# rf_tx_pa.net
KiCad netlist of a schematic drawn in Altium Designer
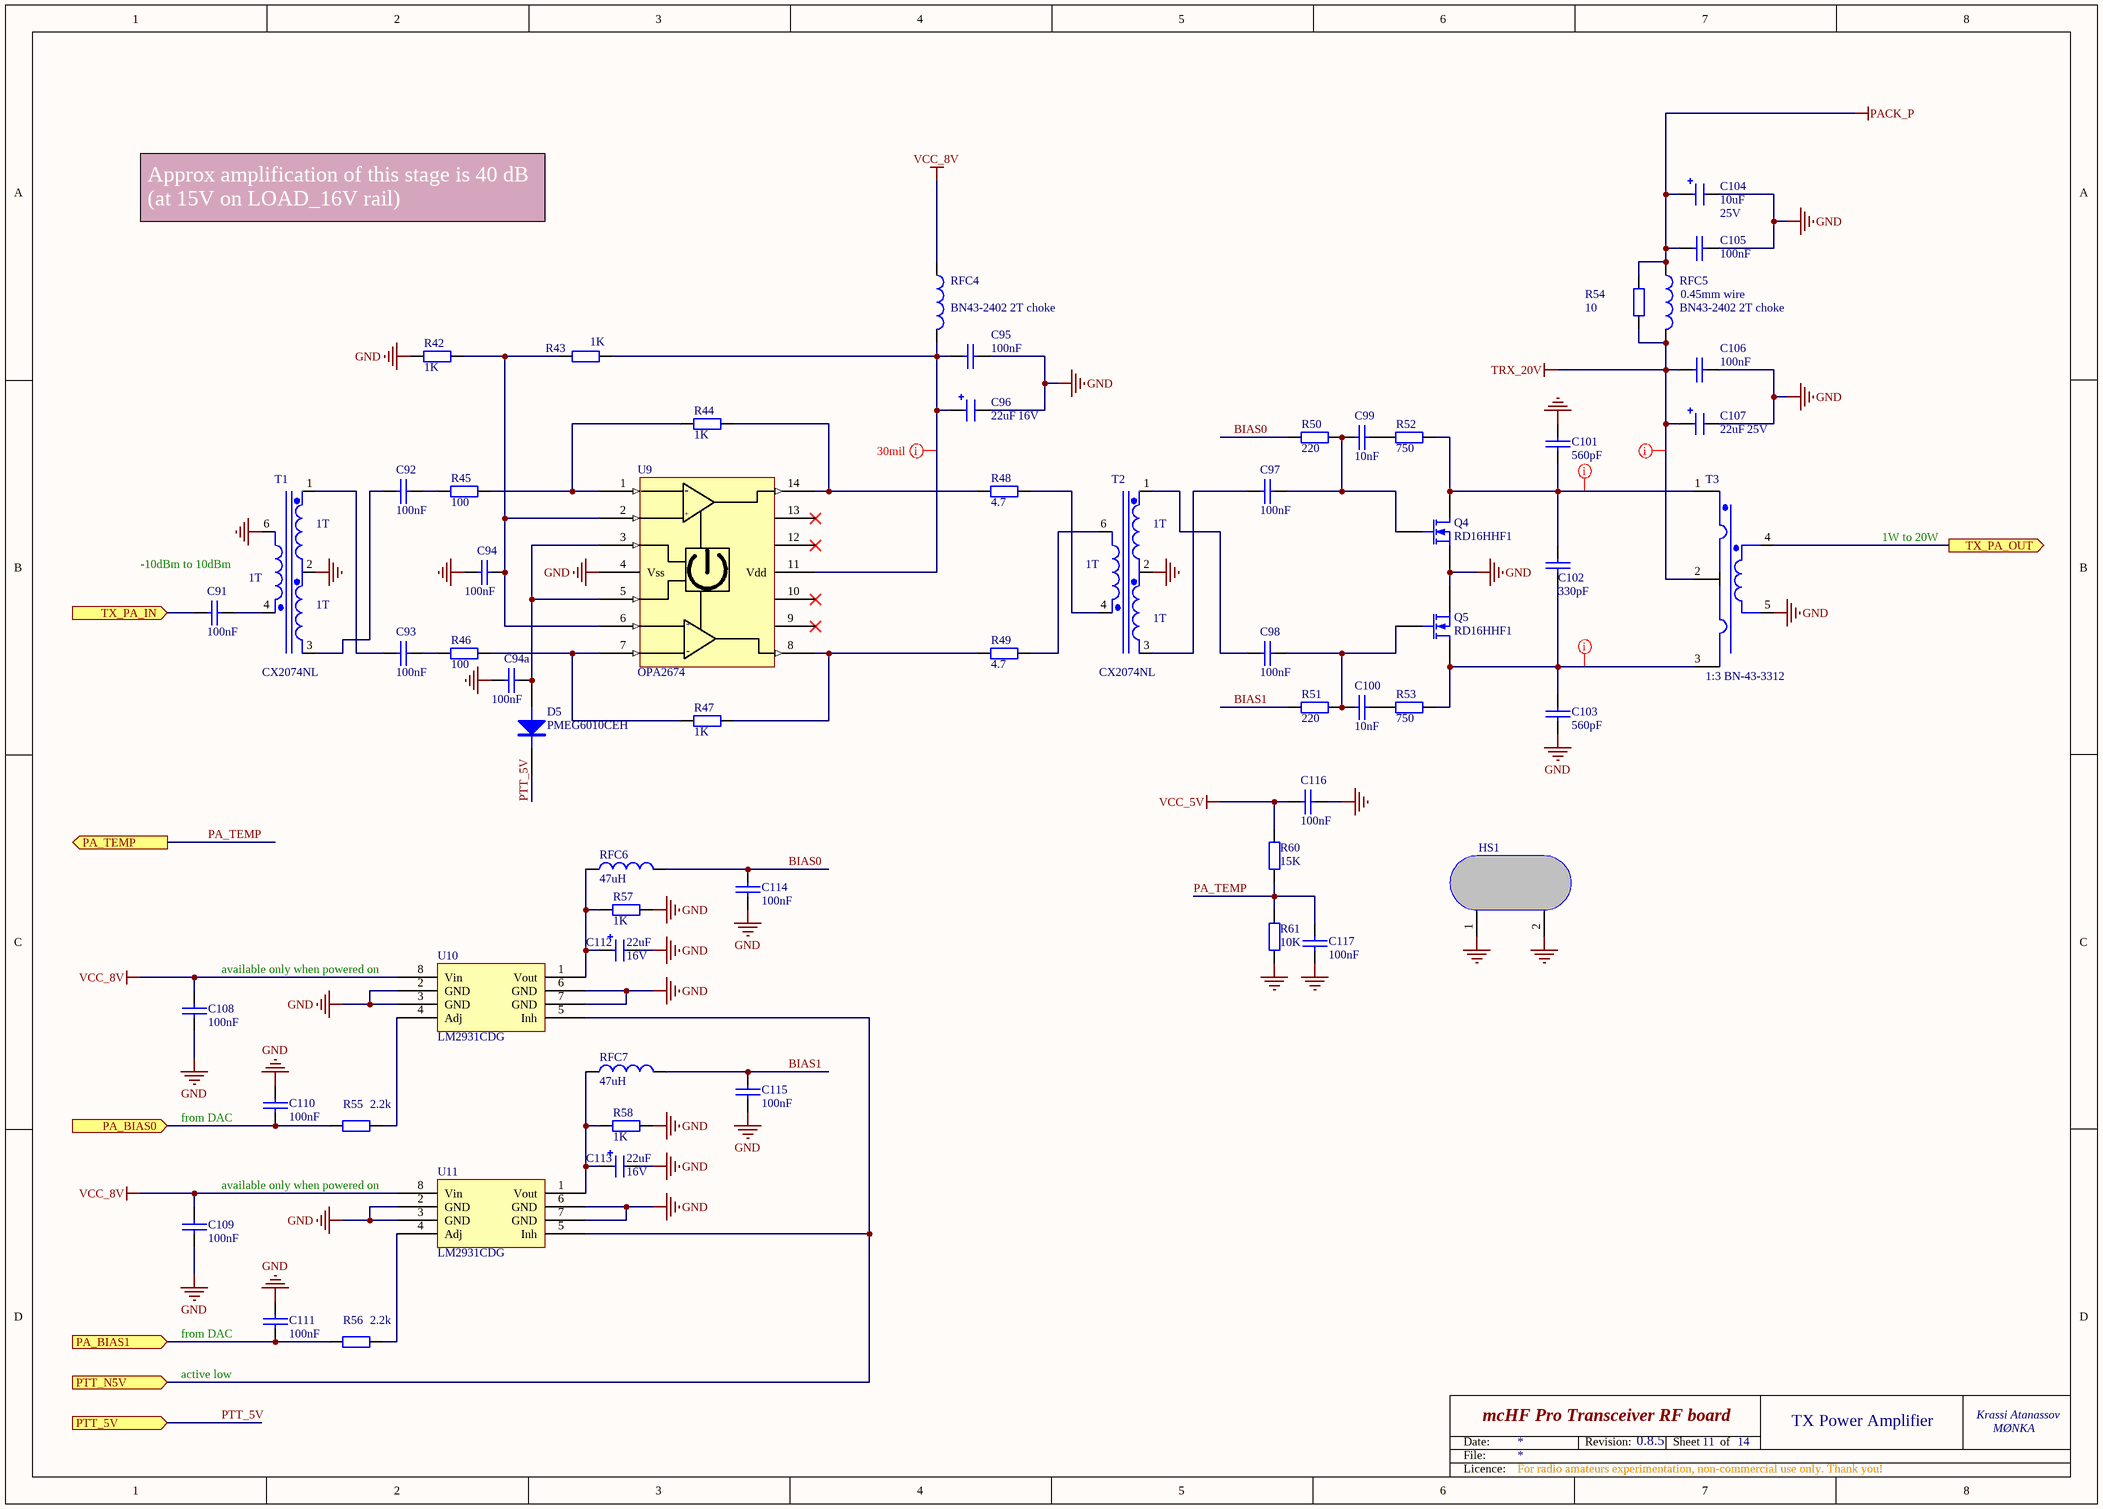
[diagram p0: rf_tx_pa.SchDoc]

(export (version "E")
  (design (tool "Eeschema 10.0.6"))
  (components
    (comp (ref "C91")
      (value "100nF")
      (footprint "0805")
      (description "Capacitor")
      (libsource (lib "mcHF_rf") (part "CAP"))
    )
    (comp (ref "C92")
      (value "100nF")
      (footprint "0805")
      (description "Capacitor")
      (fields (field (name "VOLTAGE") "100V"))
      (libsource (lib "mcHF_rf") (part "CAP"))
    )
    (comp (ref "C93")
      (value "100nF")
      (footprint "0805")
      (description "Capacitor")
      (fields (field (name "VOLTAGE") "100V"))
      (libsource (lib "mcHF_rf") (part "CAP"))
    )
    (comp (ref "C94")
      (value "100nF")
      (footprint "0805")
      (description "Capacitor")
      (fields (field (name "VOLTAGE") "100V"))
      (libsource (lib "mcHF_rf") (part "CAP"))
    )
    (comp (ref "C94a")
      (value "100nF")
      (footprint "0805")
      (description "Capacitor")
      (fields (field (name "VOLTAGE") "100V"))
      (libsource (lib "mcHF_rf") (part "CAP"))
    )
    (comp (ref "C95")
      (value "100nF")
      (footprint "0805")
      (description "Capacitor")
      (fields (field (name "VOLTAGE") "100V"))
      (libsource (lib "mcHF_rf") (part "CAP"))
    )
    (comp (ref "C96")
      (value "22uF")
      (footprint "1206_Elec_Cap")
      (description "Electrolitic capacitor")
      (fields (field (name "VOLTAGE") "16V"))
      (libsource (lib "mcHF_rf") (part "CAP-POL"))
    )
    (comp (ref "C97")
      (value "100nF")
      (footprint "0805")
      (description "Capacitor")
      (fields (field (name "VOLTAGE") "100V"))
      (libsource (lib "mcHF_rf") (part "CAP"))
    )
    (comp (ref "C98")
      (value "100nF")
      (footprint "0805")
      (description "Capacitor")
      (fields (field (name "VOLTAGE") "100V"))
      (libsource (lib "mcHF_rf") (part "CAP"))
    )
    (comp (ref "C99")
      (value "10nF")
      (footprint "0805")
      (description "Capacitor")
      (fields (field (name "VOLTAGE") "100V"))
      (libsource (lib "mcHF_rf") (part "CAP"))
    )
    (comp (ref "C100")
      (value "10nF")
      (footprint "0805")
      (description "Capacitor")
      (fields (field (name "VOLTAGE") "100V"))
      (libsource (lib "mcHF_rf") (part "CAP"))
    )
    (comp (ref "C101")
      (value "560pF")
      (footprint "0805")
      (description "Capacitor")
      (fields (field (name "VOLTAGE") "100V"))
      (libsource (lib "mcHF_rf") (part "CAP"))
    )
    (comp (ref "C102")
      (value "330pF")
      (footprint "0805")
      (description "Capacitor")
      (fields (field (name "VOLTAGE") "100V"))
      (libsource (lib "mcHF_rf") (part "CAP"))
    )
    (comp (ref "C103")
      (value "560pF")
      (footprint "0805")
      (description "Capacitor")
      (fields (field (name "VOLTAGE") "100V"))
      (libsource (lib "mcHF_rf") (part "CAP"))
    )
    (comp (ref "C104")
      (value "10uF")
      (footprint "1206_Elec_Cap")
      (description "Electrolitic capacitor")
      (fields (field (name "VOLTAGE") "25V"))
      (libsource (lib "mcHF_rf") (part "CAP-POL"))
    )
    (comp (ref "C105")
      (value "100nF")
      (footprint "0805")
      (description "Capacitor")
      (fields (field (name "VOLTAGE") "100V"))
      (libsource (lib "mcHF_rf") (part "CAP"))
    )
    (comp (ref "C106")
      (value "100nF")
      (footprint "0805")
      (description "Capacitor")
      (fields (field (name "VOLTAGE") "100V"))
      (libsource (lib "mcHF_rf") (part "CAP"))
    )
    (comp (ref "C107")
      (value "22uF")
      (footprint "1206_Elec_Cap")
      (description "Electrolitic capacitor")
      (fields (field (name "VOLTAGE") "25V"))
      (libsource (lib "mcHF_rf") (part "CAP-POL"))
    )
    (comp (ref "C108")
      (value "100nF")
      (footprint "0805")
      (description "Capacitor")
      (fields (field (name "VOLTAGE") "100V"))
      (libsource (lib "mcHF_rf") (part "CAP"))
    )
    (comp (ref "C109")
      (value "100nF")
      (footprint "0805")
      (description "Capacitor")
      (fields (field (name "VOLTAGE") "100V"))
      (libsource (lib "mcHF_rf") (part "CAP"))
    )
    (comp (ref "C110")
      (value "100nF")
      (footprint "0805")
      (description "Capacitor")
      (libsource (lib "mcHF_rf") (part "CAP"))
    )
    (comp (ref "C111")
      (value "100nF")
      (footprint "0805")
      (description "Capacitor")
      (libsource (lib "mcHF_rf") (part "CAP"))
    )
    (comp (ref "C112")
      (value "22uF")
      (footprint "1206_Elec_Cap")
      (description "Electrolitic capacitor")
      (fields (field (name "VOLTAGE") "16V"))
      (libsource (lib "mcHF_rf") (part "CAP-POL"))
    )
    (comp (ref "C113")
      (value "22uF")
      (footprint "1206_Elec_Cap")
      (description "Electrolitic capacitor")
      (fields (field (name "VOLTAGE") "16V"))
      (libsource (lib "mcHF_rf") (part "CAP-POL"))
    )
    (comp (ref "C114")
      (value "100nF")
      (footprint "0805")
      (description "Capacitor")
      (fields (field (name "VOLTAGE") "100V"))
      (libsource (lib "mcHF_rf") (part "CAP"))
    )
    (comp (ref "C115")
      (value "100nF")
      (footprint "0805")
      (description "Capacitor")
      (fields (field (name "VOLTAGE") "100V"))
      (libsource (lib "mcHF_rf") (part "CAP"))
    )
    (comp (ref "C116")
      (value "100nF")
      (footprint "0805")
      (description "Capacitor")
      (fields (field (name "VOLTAGE") "100V"))
      (libsource (lib "mcHF_rf") (part "CAP"))
    )
    (comp (ref "C117")
      (value "100nF")
      (footprint "0805")
      (description "Capacitor")
      (fields (field (name "VOLTAGE") "100V"))
      (libsource (lib "mcHF_rf") (part "CAP"))
    )
    (comp (ref "D5")
      (value "PMEG6010CEH")
      (footprint "SOD87")
      (description "DIODE, SCHOTTKY, 1A, 60V, SOD-123F")
      (libsource (lib "mcHF_rf") (part "PMEG6010CEH"))
    )
    (comp (ref "HS1")
      (value "RD16HHF1x2")
      (footprint "TO-220_5_DUAL_HS")
      (description "RF MOSFET x2 heatsink")
      (libsource (lib "__rf") (part "RD16HHF1_DUAL_HEATSINK"))
    )
    (comp (ref "Q4")
      (value "RD16HHF1")
      (footprint "TO-220c")
      (description "Silicon RF Power MOS FET")
      (libsource (lib "__rf") (part "RD16HHF1"))
    )
    (comp (ref "Q5")
      (value "RD16HHF1")
      (footprint "TO-220c")
      (description "Silicon RF Power MOS FET")
      (libsource (lib "__rf") (part "RD16HHF1"))
    )
    (comp (ref "R42")
      (value "1K")
      (footprint "0805")
      (description "Resistor")
      (libsource (lib "") (part "RES_2"))
    )
    (comp (ref "R43")
      (value "1K")
      (footprint "0805")
      (description "Resistor")
      (libsource (lib "mcHF_rf") (part "RES"))
    )
    (comp (ref "R44")
      (value "1K")
      (footprint "0805")
      (description "Resistor")
      (libsource (lib "mcHF_rf") (part "RES"))
    )
    (comp (ref "R45")
      (value "100")
      (footprint "0805")
      (description "Resistor")
      (libsource (lib "mcHF_rf") (part "RES"))
    )
    (comp (ref "R46")
      (value "100")
      (footprint "0805")
      (description "Resistor")
      (libsource (lib "mcHF_rf") (part "RES"))
    )
    (comp (ref "R47")
      (value "1K")
      (footprint "0805")
      (description "Resistor")
      (libsource (lib "mcHF_rf") (part "RES"))
    )
    (comp (ref "R48")
      (value "4.7")
      (footprint "0805")
      (description "Resistor")
      (libsource (lib "mcHF_rf") (part "RES"))
    )
    (comp (ref "R49")
      (value "4.7")
      (footprint "0805")
      (description "Resistor")
      (libsource (lib "mcHF_rf") (part "RES"))
    )
    (comp (ref "R50")
      (value "220")
      (footprint "0805")
      (description "Resistor")
      (libsource (lib "mcHF_rf") (part "RES"))
    )
    (comp (ref "R51")
      (value "220")
      (footprint "0805")
      (description "Resistor")
      (libsource (lib "mcHF_rf") (part "RES"))
    )
    (comp (ref "R52")
      (value "750")
      (footprint "0805")
      (description "Resistor")
      (libsource (lib "mcHF_rf") (part "RES"))
    )
    (comp (ref "R53")
      (value "750")
      (footprint "0805")
      (description "Resistor")
      (libsource (lib "mcHF_rf") (part "RES"))
    )
    (comp (ref "R54")
      (value "10")
      (footprint "0805")
      (description "Resistor")
      (libsource (lib "") (part "RES_3"))
    )
    (comp (ref "R55")
      (value "2.2k")
      (footprint "0805")
      (description "Resistor")
      (libsource (lib "") (part "RES_2"))
    )
    (comp (ref "R56")
      (value "2.2k")
      (footprint "0805")
      (description "Resistor")
      (libsource (lib "") (part "RES_2"))
    )
    (comp (ref "R57")
      (value "1K")
      (footprint "0805")
      (description "Resistor")
      (libsource (lib "mcHF_rf") (part "RES"))
    )
    (comp (ref "R58")
      (value "1K")
      (footprint "0805")
      (description "Resistor")
      (libsource (lib "mcHF_rf") (part "RES"))
    )
    (comp (ref "R60")
      (value "15K")
      (footprint "0805")
      (description "Resistor")
      (libsource (lib "") (part "RES_1"))
    )
    (comp (ref "R61")
      (value "10K")
      (footprint "0805")
      (description "Resistor")
      (libsource (lib "") (part "RES_1"))
    )
    (comp (ref "RFC4")
      (value "BN43-2402 2T choke")
      (footprint "F_Bead_Flat")
      (description "BN43-2402 1t choke")
      (libsource (lib "mcHF_rf") (part "FER_BEAD"))
    )
    (comp (ref "RFC5")
      (value "BN43-2402 2T choke")
      (footprint "F_Bead")
      (description "BN43-2402 1t choke")
      (libsource (lib "mcHF_rf") (part "FER_BEAD"))
    )
    (comp (ref "RFC6")
      (value "47uH")
      (footprint "0805")
      (description "INDUCTOR, SIGNAL LINE, 4.7UH, 1005")
      (libsource (lib "mcHF_rf") (part "TDK-NLV25T"))
    )
    (comp (ref "RFC7")
      (value "47uH")
      (footprint "0805")
      (description "INDUCTOR, SIGNAL LINE, 4.7UH, 1005")
      (libsource (lib "mcHF_rf") (part "TDK-NLV25T"))
    )
    (comp (ref "T1")
      (value "CX2074NL")
      (footprint "SOP5_NEW1")
      (description "Transformer 4:1")
      (libsource (lib "mcHF_rf") (part "CX2074NL"))
    )
    (comp (ref "T2")
      (value "CX2074NL")
      (footprint "SOP5_NEW1")
      (description "Transformer 4:1")
      (libsource (lib "mcHF_rf") (part "CX2074NL"))
    )
    (comp (ref "T3")
      (value "1:3 BN-43-3312")
      (footprint "PA_OUT_TRM")
      (description "1:3 BN-43-3312 transformer")
      (libsource (lib "__rf") (part "PA_OUT_TR"))
    )
    (comp (ref "U9")
      (value "OPA2674")
      (footprint "SO-14-PRO")
      (description "Dual Wideband, High Output Current\r\nOperational Amplifier with Current Limit")
      (libsource (lib "__rf") (part "OPA2674"))
    )
    (comp (ref "U10")
      (value "LM2931CDG")
      (footprint "SO-8-PRO")
      (description "100 mA, Adjustable Output,  LDO Voltage Regulator with  60 V Load Dump Protection")
      (libsource (lib "mcHF_rf") (part "LM2931CDG"))
    )
    (comp (ref "U11")
      (value "LM2931CDG")
      (footprint "SO-8-PRO")
      (description "100 mA, Adjustable Output,  LDO Voltage Regulator with  60 V Load Dump Protection")
      (libsource (lib "mcHF_rf") (part "LM2931CDG"))
    )
  )
  (nets
    (net (code "1") (name "/BIAS0") (class "Default")
      (node (ref "C114") (pin "2") (pinfunction "2_2") (pintype "passive"))
      (node (ref "R50") (pin "2") (pinfunction "2_2") (pintype "passive"))
      (node (ref "RFC6") (pin "2") (pinfunction "2_2") (pintype "passive"))
    )
    (net (code "2") (name "/BIAS1") (class "Default")
      (node (ref "C115") (pin "2") (pinfunction "2_2") (pintype "passive"))
      (node (ref "R51") (pin "2") (pinfunction "2_2") (pintype "passive"))
      (node (ref "RFC7") (pin "2") (pinfunction "2_2") (pintype "passive"))
    )
    (net (code "3") (name "/PA_BIAS0") (class "Default")
      (node (ref "C110") (pin "1") (pinfunction "1_1") (pintype "passive"))
      (node (ref "R55") (pin "1") (pinfunction "1_1") (pintype "passive"))
    )
    (net (code "4") (name "/PA_BIAS1") (class "Default")
      (node (ref "C111") (pin "2") (pinfunction "2_2") (pintype "passive"))
      (node (ref "R56") (pin "1") (pinfunction "1_1") (pintype "passive"))
    )
    (net (code "5") (name "/PA_TEMP") (class "Default")
      (node (ref "C117") (pin "1") (pinfunction "1_1") (pintype "passive"))
      (node (ref "R60") (pin "2") (pinfunction "2_2") (pintype "passive"))
      (node (ref "R61") (pin "1") (pinfunction "1_1") (pintype "passive"))
    )
    (net (code "6") (name "/PTT_5V") (class "Default")
      (node (ref "D5") (pin "2") (pinfunction "K_2") (pintype "passive"))
    )
    (net (code "7") (name "/PTT_N5V") (class "Default")
      (node (ref "U10") (pin "5") (pinfunction "Inh_5") (pintype "passive"))
      (node (ref "U11") (pin "5") (pinfunction "Inh_5") (pintype "passive"))
    )
    (net (code "8") (name "/TX_PA_IN") (class "Default")
      (node (ref "C91") (pin "2") (pinfunction "2_2") (pintype "passive"))
    )
    (net (code "9") (name "/TX_PA_OUT") (class "Default")
      (node (ref "T3") (pin "4") (pinfunction "Sec+_4") (pintype "passive"))
    )
    (net (code "10") (name "GND") (class "Default")
      (node (ref "C101") (pin "1") (pinfunction "1_1") (pintype "passive"))
      (node (ref "C103") (pin "2") (pinfunction "2_2") (pintype "passive"))
      (node (ref "C104") (pin "2") (pinfunction "2_2") (pintype "passive"))
      (node (ref "C105") (pin "1") (pinfunction "1_1") (pintype "passive"))
      (node (ref "C106") (pin "1") (pinfunction "1_1") (pintype "passive"))
      (node (ref "C107") (pin "2") (pinfunction "2_2") (pintype "passive"))
      (node (ref "C108") (pin "2") (pinfunction "2_2") (pintype "passive"))
      (node (ref "C109") (pin "2") (pinfunction "2_2") (pintype "passive"))
      (node (ref "C110") (pin "2") (pinfunction "2_2") (pintype "passive"))
      (node (ref "C111") (pin "1") (pinfunction "1_1") (pintype "passive"))
      (node (ref "C112") (pin "2") (pinfunction "2_2") (pintype "passive"))
      (node (ref "C113") (pin "2") (pinfunction "2_2") (pintype "passive"))
      (node (ref "C114") (pin "1") (pinfunction "1_1") (pintype "passive"))
      (node (ref "C115") (pin "1") (pinfunction "1_1") (pintype "passive"))
      (node (ref "C116") (pin "1") (pinfunction "1_1") (pintype "passive"))
      (node (ref "C117") (pin "2") (pinfunction "2_2") (pintype "passive"))
      (node (ref "C94") (pin "1") (pinfunction "1_1") (pintype "passive"))
      (node (ref "C94a") (pin "1") (pinfunction "1_1") (pintype "passive"))
      (node (ref "C95") (pin "1") (pinfunction "1_1") (pintype "passive"))
      (node (ref "C96") (pin "2") (pinfunction "2_2") (pintype "passive"))
      (node (ref "HS1") (pin "1") (pinfunction "GND_1") (pintype "passive"))
      (node (ref "HS1") (pin "2") (pinfunction "GND_2") (pintype "passive"))
      (node (ref "Q4") (pin "2") (pinfunction "S_2") (pintype "passive"))
      (node (ref "Q5") (pin "2") (pinfunction "S_2") (pintype "passive"))
      (node (ref "R42") (pin "1") (pinfunction "1_1") (pintype "passive"))
      (node (ref "R57") (pin "1") (pinfunction "1_1") (pintype "passive"))
      (node (ref "R58") (pin "1") (pinfunction "1_1") (pintype "passive"))
      (node (ref "R61") (pin "2") (pinfunction "2_2") (pintype "passive"))
      (node (ref "T1") (pin "2") (pinfunction "SecCmn_2") (pintype "passive"))
      (node (ref "T1") (pin "6") (pinfunction "Pri+_6") (pintype "passive"))
      (node (ref "T2") (pin "2") (pinfunction "SecCmn_2") (pintype "passive"))
      (node (ref "T3") (pin "5") (pinfunction "Sec-_5") (pintype "passive"))
      (node (ref "U10") (pin "2") (pinfunction "GND_2") (pintype "passive"))
      (node (ref "U10") (pin "3") (pinfunction "GND_3") (pintype "passive"))
      (node (ref "U10") (pin "6") (pinfunction "GND_6") (pintype "passive"))
      (node (ref "U10") (pin "7") (pinfunction "GND_7") (pintype "passive"))
      (node (ref "U11") (pin "2") (pinfunction "GND_2") (pintype "passive"))
      (node (ref "U11") (pin "3") (pinfunction "GND_3") (pintype "passive"))
      (node (ref "U11") (pin "6") (pinfunction "GND_6") (pintype "passive"))
      (node (ref "U11") (pin "7") (pinfunction "GND_7") (pintype "passive"))
      (node (ref "U9") (pin "4") (pinfunction "Vss_4") (pintype "power_in"))
    )
    (net (code "11") (name "Net-(C92-Pad2)") (class "Default")
      (node (ref "C92") (pin "2") (pinfunction "2_2") (pintype "passive"))
      (node (ref "R45") (pin "2") (pinfunction "2_2") (pintype "passive"))
    )
    (net (code "12") (name "Net-(C93-Pad2)") (class "Default")
      (node (ref "C93") (pin "2") (pinfunction "2_2") (pintype "passive"))
      (node (ref "R46") (pin "2") (pinfunction "2_2") (pintype "passive"))
    )
    (net (code "13") (name "Net-(C94-Pad2)") (class "Default")
      (node (ref "C94") (pin "2") (pinfunction "2_2") (pintype "passive"))
      (node (ref "R42") (pin "2") (pinfunction "2_2") (pintype "passive"))
      (node (ref "R43") (pin "2") (pinfunction "2_2") (pintype "passive"))
      (node (ref "U9") (pin "2") (pintype "input"))
      (node (ref "U9") (pin "6") (pintype "input"))
    )
    (net (code "14") (name "Net-(C99-Pad2)") (class "Default")
      (node (ref "C99") (pin "2") (pinfunction "2_2") (pintype "passive"))
      (node (ref "R52") (pin "2") (pinfunction "2_2") (pintype "passive"))
    )
    (net (code "15") (name "Net-(C100-Pad2)") (class "Default")
      (node (ref "C100") (pin "2") (pinfunction "2_2") (pintype "passive"))
      (node (ref "R53") (pin "2") (pinfunction "2_2") (pintype "passive"))
    )
    (net (code "16") (name "Net-(D5-A)") (class "Default")
      (node (ref "C94a") (pin "2") (pinfunction "2_2") (pintype "passive"))
      (node (ref "D5") (pin "1") (pinfunction "A_1") (pintype "passive"))
      (node (ref "U9") (pin "3") (pintype "input"))
      (node (ref "U9") (pin "5") (pintype "input"))
    )
    (net (code "17") (name "Net-(Q4-D)") (class "Default")
      (node (ref "C101") (pin "2") (pinfunction "2_2") (pintype "passive"))
      (node (ref "C102") (pin "1") (pinfunction "1_1") (pintype "passive"))
      (node (ref "Q4") (pin "3") (pinfunction "D_3") (pintype "passive"))
      (node (ref "R52") (pin "1") (pinfunction "1_1") (pintype "passive"))
      (node (ref "T3") (pin "1") (pinfunction "Pri_0_deg_1") (pintype "passive"))
    )
    (net (code "18") (name "Net-(Q4-G)") (class "Default")
      (node (ref "C97") (pin "1") (pinfunction "1_1") (pintype "passive"))
      (node (ref "C99") (pin "1") (pinfunction "1_1") (pintype "passive"))
      (node (ref "Q4") (pin "1") (pinfunction "G_1") (pintype "passive"))
      (node (ref "R50") (pin "1") (pinfunction "1_1") (pintype "passive"))
    )
    (net (code "19") (name "Net-(Q5-D)") (class "Default")
      (node (ref "C102") (pin "2") (pinfunction "2_2") (pintype "passive"))
      (node (ref "C103") (pin "1") (pinfunction "1_1") (pintype "passive"))
      (node (ref "Q5") (pin "3") (pinfunction "D_3") (pintype "passive"))
      (node (ref "R53") (pin "1") (pinfunction "1_1") (pintype "passive"))
      (node (ref "T3") (pin "3") (pinfunction "Pri_180_deg_3") (pintype "passive"))
    )
    (net (code "20") (name "Net-(Q5-G)") (class "Default")
      (node (ref "C100") (pin "1") (pinfunction "1_1") (pintype "passive"))
      (node (ref "C98") (pin "1") (pinfunction "1_1") (pintype "passive"))
      (node (ref "Q5") (pin "1") (pinfunction "G_1") (pintype "passive"))
      (node (ref "R51") (pin "1") (pinfunction "1_1") (pintype "passive"))
    )
    (net (code "21") (name "Net-(R44-Pad1)") (class "Default")
      (node (ref "R44") (pin "1") (pinfunction "1_1") (pintype "passive"))
      (node (ref "R48") (pin "2") (pinfunction "2_2") (pintype "passive"))
      (node (ref "U9") (pin "14") (pintype "output"))
    )
    (net (code "22") (name "Net-(R44-Pad2)") (class "Default")
      (node (ref "R44") (pin "2") (pinfunction "2_2") (pintype "passive"))
      (node (ref "R45") (pin "1") (pinfunction "1_1") (pintype "passive"))
      (node (ref "U9") (pin "1") (pintype "input"))
    )
    (net (code "23") (name "Net-(R46-Pad1)") (class "Default")
      (node (ref "R46") (pin "1") (pinfunction "1_1") (pintype "passive"))
      (node (ref "R47") (pin "2") (pinfunction "2_2") (pintype "passive"))
      (node (ref "U9") (pin "7") (pintype "input"))
    )
    (net (code "24") (name "Net-(R47-Pad1)") (class "Default")
      (node (ref "R47") (pin "1") (pinfunction "1_1") (pintype "passive"))
      (node (ref "R49") (pin "2") (pinfunction "2_2") (pintype "passive"))
      (node (ref "U9") (pin "8") (pintype "output"))
    )
    (net (code "25") (name "Net-(T1-Pri-)") (class "Default")
      (node (ref "C91") (pin "1") (pinfunction "1_1") (pintype "passive"))
      (node (ref "T1") (pin "4") (pinfunction "Pri-_4") (pintype "passive"))
    )
    (net (code "26") (name "Net-(T1-Sec0)") (class "Default")
      (node (ref "C93") (pin "1") (pinfunction "1_1") (pintype "passive"))
      (node (ref "T1") (pin "1") (pinfunction "Sec0_1") (pintype "passive"))
    )
    (net (code "27") (name "Net-(T1-Sec180)") (class "Default")
      (node (ref "C92") (pin "1") (pinfunction "1_1") (pintype "passive"))
      (node (ref "T1") (pin "3") (pinfunction "Sec180_3") (pintype "passive"))
    )
    (net (code "28") (name "Net-(T2-Pri+)") (class "Default")
      (node (ref "R49") (pin "1") (pinfunction "1_1") (pintype "passive"))
      (node (ref "T2") (pin "6") (pinfunction "Pri+_6") (pintype "passive"))
    )
    (net (code "29") (name "Net-(T2-Pri-)") (class "Default")
      (node (ref "R48") (pin "1") (pinfunction "1_1") (pintype "passive"))
      (node (ref "T2") (pin "4") (pinfunction "Pri-_4") (pintype "passive"))
    )
    (net (code "30") (name "Net-(T2-Sec0)") (class "Default")
      (node (ref "C98") (pin "2") (pinfunction "2_2") (pintype "passive"))
      (node (ref "T2") (pin "1") (pinfunction "Sec0_1") (pintype "passive"))
    )
    (net (code "31") (name "Net-(T2-Sec180)") (class "Default")
      (node (ref "C97") (pin "2") (pinfunction "2_2") (pintype "passive"))
      (node (ref "T2") (pin "3") (pinfunction "Sec180_3") (pintype "passive"))
    )
    (net (code "32") (name "Net-(U9-Vdd)") (class "Default")
      (node (ref "C95") (pin "2") (pinfunction "2_2") (pintype "passive"))
      (node (ref "C96") (pin "1") (pinfunction "1_1") (pintype "passive"))
      (node (ref "R43") (pin "1") (pinfunction "1_1") (pintype "passive"))
      (node (ref "RFC4") (pin "2") (pinfunction "2_2") (pintype "passive"))
      (node (ref "U9") (pin "11") (pinfunction "Vdd_11") (pintype "power_in"))
    )
    (net (code "33") (name "Net-(U10-Adj)") (class "Default")
      (node (ref "R55") (pin "2") (pinfunction "2_2") (pintype "passive"))
      (node (ref "U10") (pin "4") (pinfunction "Adj_4") (pintype "passive"))
    )
    (net (code "34") (name "Net-(U10-Vout)") (class "Default")
      (node (ref "C112") (pin "1") (pinfunction "1_1") (pintype "passive"))
      (node (ref "R57") (pin "2") (pinfunction "2_2") (pintype "passive"))
      (node (ref "RFC6") (pin "1") (pinfunction "1_1") (pintype "passive"))
      (node (ref "U10") (pin "1") (pinfunction "Vout_1") (pintype "passive"))
    )
    (net (code "35") (name "Net-(U11-Adj)") (class "Default")
      (node (ref "R56") (pin "2") (pinfunction "2_2") (pintype "passive"))
      (node (ref "U11") (pin "4") (pinfunction "Adj_4") (pintype "passive"))
    )
    (net (code "36") (name "Net-(U11-Vout)") (class "Default")
      (node (ref "C113") (pin "1") (pinfunction "1_1") (pintype "passive"))
      (node (ref "R58") (pin "2") (pinfunction "2_2") (pintype "passive"))
      (node (ref "RFC7") (pin "1") (pinfunction "1_1") (pintype "passive"))
      (node (ref "U11") (pin "1") (pinfunction "Vout_1") (pintype "passive"))
    )
    (net (code "37") (name "PACK_P") (class "Default")
      (node (ref "C104") (pin "1") (pinfunction "1_1") (pintype "passive"))
      (node (ref "C105") (pin "2") (pinfunction "2_2") (pintype "passive"))
      (node (ref "R54") (pin "2") (pinfunction "2_2") (pintype "passive"))
      (node (ref "RFC5") (pin "1") (pinfunction "1_1") (pintype "passive"))
    )
    (net (code "38") (name "TRX_20V") (class "Default")
      (node (ref "C106") (pin "2") (pinfunction "2_2") (pintype "passive"))
      (node (ref "C107") (pin "1") (pinfunction "1_1") (pintype "passive"))
      (node (ref "R54") (pin "1") (pinfunction "1_1") (pintype "passive"))
      (node (ref "RFC5") (pin "2") (pinfunction "2_2") (pintype "passive"))
      (node (ref "T3") (pin "2") (pinfunction "Pri_Common_2") (pintype "passive"))
    )
    (net (code "39") (name "VCC_5V") (class "Default")
      (node (ref "C116") (pin "2") (pinfunction "2_2") (pintype "passive"))
      (node (ref "R60") (pin "1") (pinfunction "1_1") (pintype "passive"))
    )
    (net (code "40") (name "VCC_8V") (class "Default")
      (node (ref "C108") (pin "1") (pinfunction "1_1") (pintype "passive"))
      (node (ref "C109") (pin "1") (pinfunction "1_1") (pintype "passive"))
      (node (ref "RFC4") (pin "1") (pinfunction "1_1") (pintype "passive"))
      (node (ref "U10") (pin "8") (pinfunction "Vin_8") (pintype "passive"))
      (node (ref "U11") (pin "8") (pinfunction "Vin_8") (pintype "passive"))
    )
    (net (code "41") (name "unconnected-(U9-Pad9)") (class "Default")
      (node (ref "U9") (pin "9") (pintype "passive+no_connect"))
    )
    (net (code "42") (name "unconnected-(U9-Pad10)") (class "Default")
      (node (ref "U9") (pin "10") (pintype "passive+no_connect"))
    )
    (net (code "43") (name "unconnected-(U9-Pad12)") (class "Default")
      (node (ref "U9") (pin "12") (pintype "passive+no_connect"))
    )
    (net (code "44") (name "unconnected-(U9-Pad13)") (class "Default")
      (node (ref "U9") (pin "13") (pintype "passive+no_connect"))
    )
  )
)
